# IOB-I2C-PCA9685-PWM.net
KiCad netlist of a schematic drawn in EAGLE
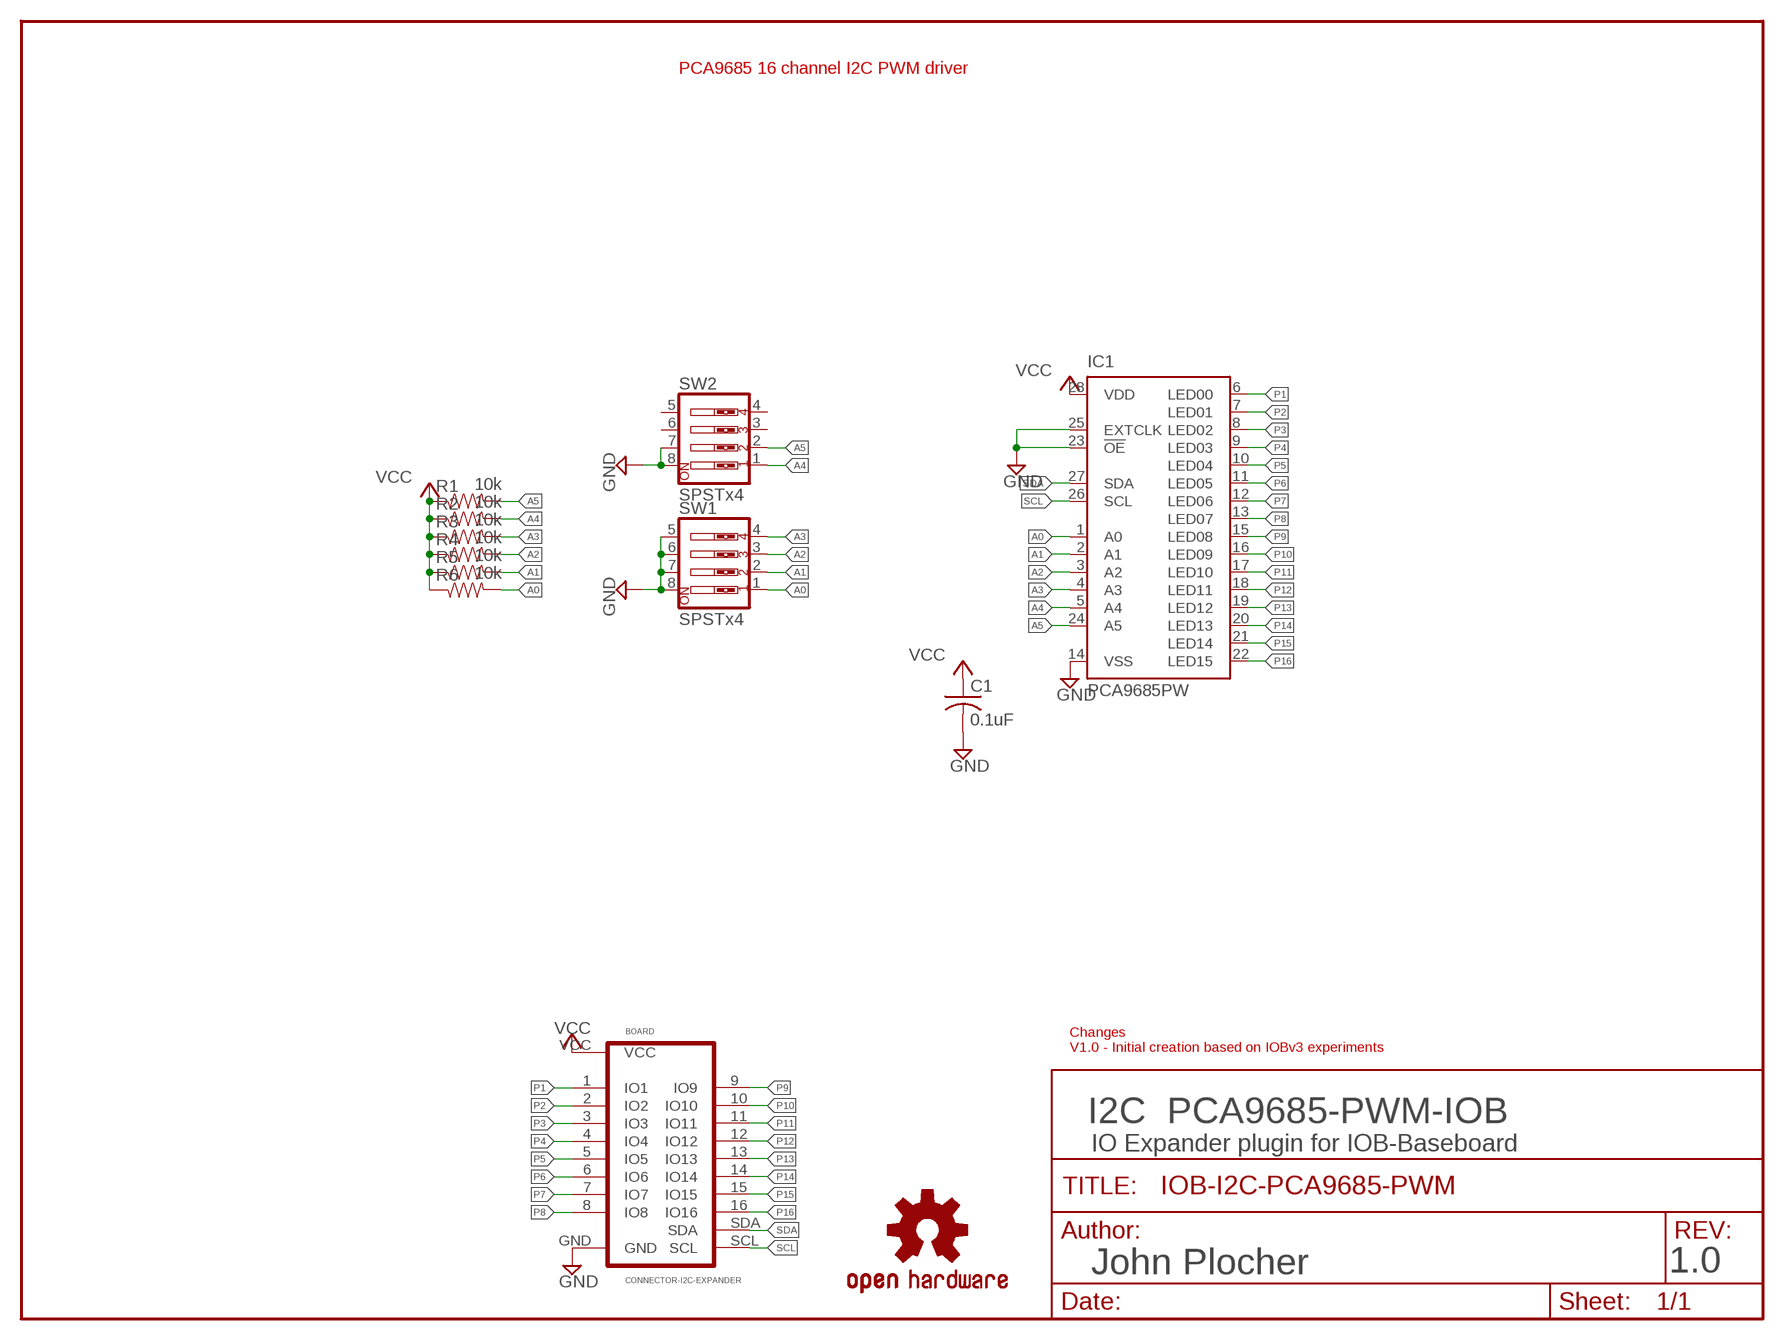
[diagram p0: schematic, sheet 1]

(export (version "E")
  (design (tool "Eeschema 10.0.6"))
  (components
    (comp (ref "BOARD")
      (value "CONNECTOR-I2C-EXPANDER")
      (footprint "eagle-import:I2C-EXPANDER")
      (libsource (lib "eagle-import") (part "CONNECTOR-I2C-EXPANDER"))
    )
    (comp (ref "C1")
      (value "0.1uF")
      (footprint "eagle-import:0603-CAP")
      (libsource (lib "eagle-import") (part "CAP0603"))
    )
    (comp (ref "IC1")
      (value "PCA9685PW")
      (footprint "eagle-import:TSSOP28")
      (libsource (lib "eagle-import") (part "PCA9685PW"))
    )
    (comp (ref "R1")
      (value "10k")
      (footprint "eagle-import:0603-RES")
      (libsource (lib "eagle-import") (part "R0603-RES"))
    )
    (comp (ref "R2")
      (value "10k")
      (footprint "eagle-import:0603-RES")
      (libsource (lib "eagle-import") (part "R0603-RES"))
    )
    (comp (ref "R3")
      (value "10k")
      (footprint "eagle-import:0603-RES")
      (libsource (lib "eagle-import") (part "R0603-RES"))
    )
    (comp (ref "R4")
      (value "10k")
      (footprint "eagle-import:0603-RES")
      (libsource (lib "eagle-import") (part "R0603-RES"))
    )
    (comp (ref "R5")
      (value "10k")
      (footprint "eagle-import:0603-RES")
      (libsource (lib "eagle-import") (part "R0603-RES"))
    )
    (comp (ref "R6")
      (value "10k")
      (footprint "eagle-import:0603-RES")
      (libsource (lib "eagle-import") (part "R0603-RES"))
    )
    (comp (ref "SW1")
      (value "SPSTx4")
      (footprint "eagle-import:EDG-04")
      (libsource (lib "eagle-import") (part "SW_DIP-4"))
    )
    (comp (ref "SW2")
      (value "SPSTx4")
      (footprint "eagle-import:EDG-04")
      (libsource (lib "eagle-import") (part "SW_DIP-4"))
    )
    (comp (ref "U$1")
      (value "OSHW")
      (footprint "eagle-import:OSHW-LOGO-L")
      (libsource (lib "eagle-import") (part "DOC-OSHW-LOGO-L"))
    )
  )
  (nets
    (net (code "1") (name "A0") (class "Default")
      (node (ref "IC1") (pin "1") (pinfunction "A0_1") (pintype "input"))
      (node (ref "R6") (pin "2") (pinfunction "2_2") (pintype "passive"))
      (node (ref "SW1") (pin "1") (pinfunction "1_1") (pintype "passive"))
    )
    (net (code "2") (name "A1") (class "Default")
      (node (ref "IC1") (pin "2") (pinfunction "A1_2") (pintype "input"))
      (node (ref "R5") (pin "2") (pinfunction "2_2") (pintype "passive"))
      (node (ref "SW1") (pin "2") (pinfunction "2_2") (pintype "passive"))
    )
    (net (code "3") (name "A2") (class "Default")
      (node (ref "IC1") (pin "3") (pinfunction "A2_3") (pintype "input"))
      (node (ref "R4") (pin "2") (pinfunction "2_2") (pintype "passive"))
      (node (ref "SW1") (pin "3") (pinfunction "3_3") (pintype "passive"))
    )
    (net (code "4") (name "A3") (class "Default")
      (node (ref "IC1") (pin "4") (pinfunction "A3_4") (pintype "input"))
      (node (ref "R3") (pin "2") (pinfunction "2_2") (pintype "passive"))
      (node (ref "SW1") (pin "4") (pinfunction "4_4") (pintype "passive"))
    )
    (net (code "5") (name "A4") (class "Default")
      (node (ref "IC1") (pin "5") (pinfunction "A4_5") (pintype "input"))
      (node (ref "R2") (pin "2") (pinfunction "2_2") (pintype "passive"))
      (node (ref "SW2") (pin "1") (pinfunction "1_1") (pintype "passive"))
    )
    (net (code "6") (name "A5") (class "Default")
      (node (ref "IC1") (pin "24") (pinfunction "A5_24") (pintype "input"))
      (node (ref "R1") (pin "2") (pinfunction "2_2") (pintype "passive"))
      (node (ref "SW2") (pin "2") (pinfunction "2_2") (pintype "passive"))
    )
    (net (code "7") (name "GND") (class "Default")
      (node (ref "BOARD") (pin "GND") (pinfunction "GND_GND") (pintype "bidirectional"))
      (node (ref "C1") (pin "2") (pinfunction "2_2") (pintype "passive"))
      (node (ref "IC1") (pin "14") (pinfunction "VSS_14") (pintype "power_in"))
      (node (ref "IC1") (pin "23") (pinfunction "~{OE}_23") (pintype "input"))
      (node (ref "IC1") (pin "25") (pinfunction "EXTCLK_25") (pintype "input"))
      (node (ref "SW1") (pin "5") (pinfunction "5_5") (pintype "passive"))
      (node (ref "SW1") (pin "6") (pinfunction "6_6") (pintype "passive"))
      (node (ref "SW1") (pin "7") (pinfunction "7_7") (pintype "passive"))
      (node (ref "SW1") (pin "8") (pinfunction "8_8") (pintype "passive"))
      (node (ref "SW2") (pin "7") (pinfunction "7_7") (pintype "passive"))
      (node (ref "SW2") (pin "8") (pinfunction "8_8") (pintype "passive"))
    )
    (net (code "8") (name "P1") (class "Default")
      (node (ref "BOARD") (pin "1") (pinfunction "IO1_1") (pintype "bidirectional"))
      (node (ref "IC1") (pin "6") (pinfunction "LED00_6") (pintype "output"))
    )
    (net (code "9") (name "P2") (class "Default")
      (node (ref "BOARD") (pin "2") (pinfunction "IO2_2") (pintype "bidirectional"))
      (node (ref "IC1") (pin "7") (pinfunction "LED01_7") (pintype "output"))
    )
    (net (code "10") (name "P3") (class "Default")
      (node (ref "BOARD") (pin "3") (pinfunction "IO3_3") (pintype "bidirectional"))
      (node (ref "IC1") (pin "8") (pinfunction "LED02_8") (pintype "output"))
    )
    (net (code "11") (name "P4") (class "Default")
      (node (ref "BOARD") (pin "4") (pinfunction "IO4_4") (pintype "bidirectional"))
      (node (ref "IC1") (pin "9") (pinfunction "LED03_9") (pintype "output"))
    )
    (net (code "12") (name "P5") (class "Default")
      (node (ref "BOARD") (pin "5") (pinfunction "IO5_5") (pintype "bidirectional"))
      (node (ref "IC1") (pin "10") (pinfunction "LED04_10") (pintype "output"))
    )
    (net (code "13") (name "P6") (class "Default")
      (node (ref "BOARD") (pin "6") (pinfunction "IO6_6") (pintype "bidirectional"))
      (node (ref "IC1") (pin "11") (pinfunction "LED05_11") (pintype "output"))
    )
    (net (code "14") (name "P7") (class "Default")
      (node (ref "BOARD") (pin "7") (pinfunction "IO7_7") (pintype "bidirectional"))
      (node (ref "IC1") (pin "12") (pinfunction "LED06_12") (pintype "output"))
    )
    (net (code "15") (name "P8") (class "Default")
      (node (ref "BOARD") (pin "8") (pinfunction "IO8_8") (pintype "bidirectional"))
      (node (ref "IC1") (pin "13") (pinfunction "LED07_13") (pintype "output"))
    )
    (net (code "16") (name "P9") (class "Default")
      (node (ref "BOARD") (pin "9") (pinfunction "IO9_9") (pintype "bidirectional"))
      (node (ref "IC1") (pin "15") (pinfunction "LED08_15") (pintype "output"))
    )
    (net (code "17") (name "P10") (class "Default")
      (node (ref "BOARD") (pin "10") (pinfunction "IO10_10") (pintype "bidirectional"))
      (node (ref "IC1") (pin "16") (pinfunction "LED09_16") (pintype "output"))
    )
    (net (code "18") (name "P11") (class "Default")
      (node (ref "BOARD") (pin "11") (pinfunction "IO11_11") (pintype "bidirectional"))
      (node (ref "IC1") (pin "17") (pinfunction "LED10_17") (pintype "output"))
    )
    (net (code "19") (name "P12") (class "Default")
      (node (ref "BOARD") (pin "12") (pinfunction "IO12_12") (pintype "bidirectional"))
      (node (ref "IC1") (pin "18") (pinfunction "LED11_18") (pintype "output"))
    )
    (net (code "20") (name "P13") (class "Default")
      (node (ref "BOARD") (pin "13") (pinfunction "IO13_13") (pintype "bidirectional"))
      (node (ref "IC1") (pin "19") (pinfunction "LED12_19") (pintype "output"))
    )
    (net (code "21") (name "P14") (class "Default")
      (node (ref "BOARD") (pin "14") (pinfunction "IO14_14") (pintype "bidirectional"))
      (node (ref "IC1") (pin "20") (pinfunction "LED13_20") (pintype "output"))
    )
    (net (code "22") (name "P15") (class "Default")
      (node (ref "BOARD") (pin "15") (pinfunction "IO15_15") (pintype "bidirectional"))
      (node (ref "IC1") (pin "21") (pinfunction "LED14_21") (pintype "output"))
    )
    (net (code "23") (name "P16") (class "Default")
      (node (ref "BOARD") (pin "16") (pinfunction "IO16_16") (pintype "bidirectional"))
      (node (ref "IC1") (pin "22") (pinfunction "LED15_22") (pintype "output"))
    )
    (net (code "24") (name "SCL") (class "Default")
      (node (ref "BOARD") (pin "SCL") (pinfunction "SCL_SCL") (pintype "bidirectional"))
      (node (ref "IC1") (pin "26") (pinfunction "SCL_26") (pintype "input"))
    )
    (net (code "25") (name "SDA") (class "Default")
      (node (ref "BOARD") (pin "SDA") (pinfunction "SDA_SDA") (pintype "bidirectional"))
      (node (ref "IC1") (pin "27") (pinfunction "SDA_27") (pintype "bidirectional"))
    )
    (net (code "26") (name "VCC") (class "Default")
      (node (ref "BOARD") (pin "VCC") (pinfunction "VCC_VCC") (pintype "bidirectional"))
      (node (ref "C1") (pin "1") (pinfunction "1_1") (pintype "passive"))
      (node (ref "IC1") (pin "28") (pinfunction "VDD_28") (pintype "power_in"))
      (node (ref "R1") (pin "1") (pinfunction "1_1") (pintype "passive"))
      (node (ref "R2") (pin "1") (pinfunction "1_1") (pintype "passive"))
      (node (ref "R3") (pin "1") (pinfunction "1_1") (pintype "passive"))
      (node (ref "R4") (pin "1") (pinfunction "1_1") (pintype "passive"))
      (node (ref "R5") (pin "1") (pinfunction "1_1") (pintype "passive"))
      (node (ref "R6") (pin "1") (pinfunction "1_1") (pintype "passive"))
    )
    (net (code "27") (name "unconnected-(SW2-Pad3)") (class "Default")
      (node (ref "SW2") (pin "3") (pinfunction "3_3") (pintype "passive"))
    )
    (net (code "28") (name "unconnected-(SW2-Pad4)") (class "Default")
      (node (ref "SW2") (pin "4") (pinfunction "4_4") (pintype "passive"))
    )
    (net (code "29") (name "unconnected-(SW2-Pad5)") (class "Default")
      (node (ref "SW2") (pin "5") (pinfunction "5_5") (pintype "passive"))
    )
    (net (code "30") (name "unconnected-(SW2-Pad6)") (class "Default")
      (node (ref "SW2") (pin "6") (pinfunction "6_6") (pintype "passive"))
    )
  )
)
